# TS-ARM3_0_8.net
KiCad netlist of a schematic drawn in EAGLE
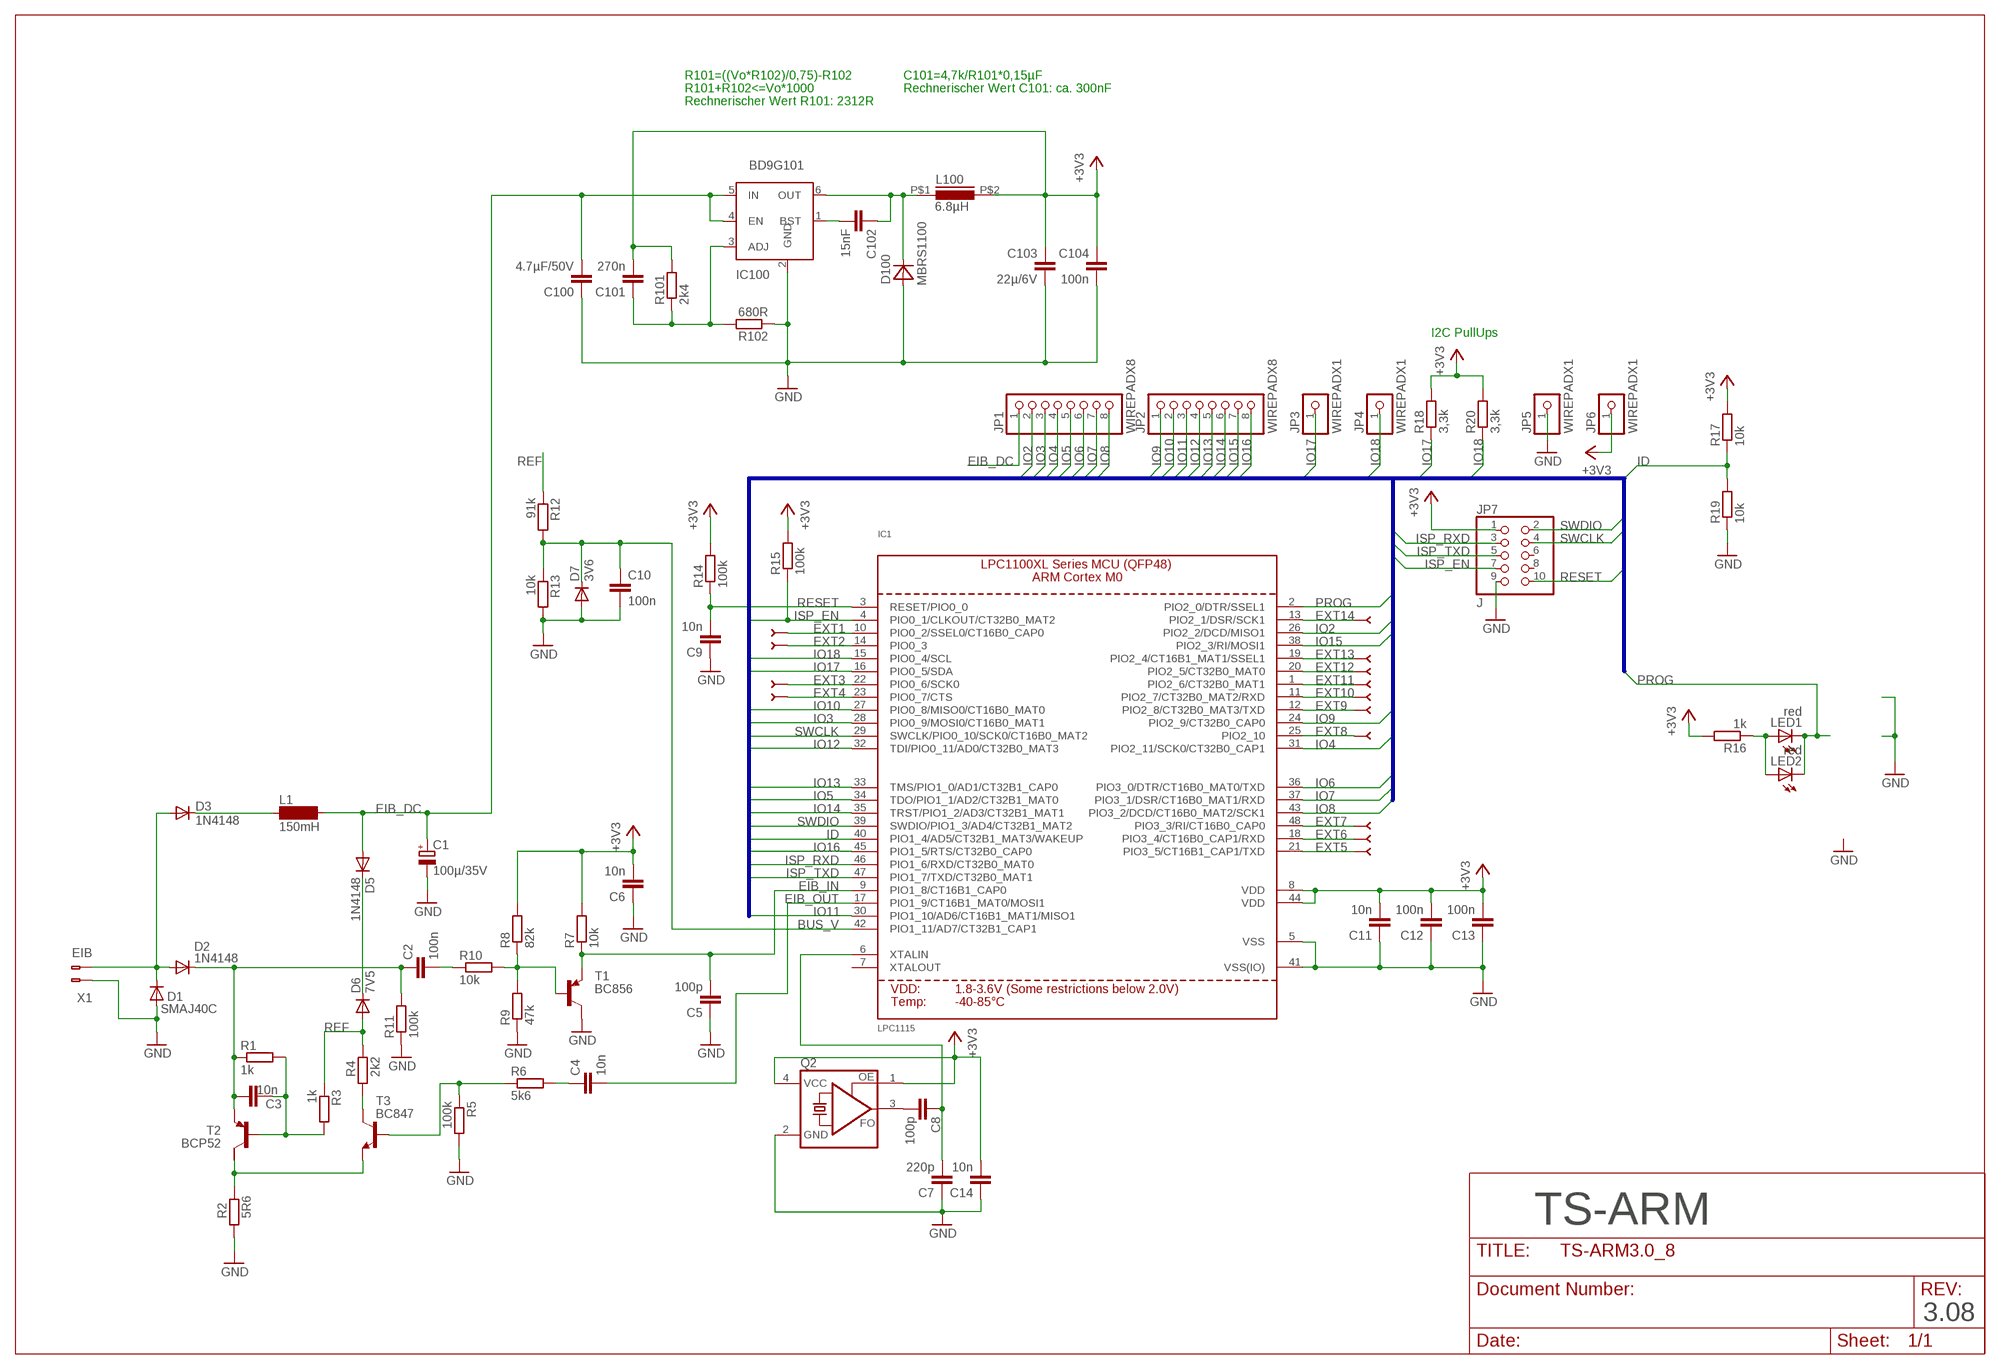
[diagram p0: schematic, sheet 1]

(export (version "E")
  (design (tool "Eeschema 10.0.6"))
  (components
    (comp (ref "C1")
      (value "100µ/35V")
      (footprint "eagle-import:SANYO-OSCON_SMD_C6")
      (libsource (lib "eagle-import") (part "CPOL-EUSANYO_SMD_C6"))
    )
    (comp (ref "C2")
      (value "100n")
      (footprint "eagle-import:C1206")
      (libsource (lib "eagle-import") (part "C-EUC1206"))
    )
    (comp (ref "C3")
      (value "10n")
      (footprint "eagle-import:C1206")
      (libsource (lib "eagle-import") (part "C-EUC1206"))
    )
    (comp (ref "C4")
      (value "10n")
      (footprint "eagle-import:C1206")
      (libsource (lib "eagle-import") (part "C-EUC1206"))
    )
    (comp (ref "C5")
      (value "100p")
      (footprint "eagle-import:C1206")
      (libsource (lib "eagle-import") (part "C-EUC1206"))
    )
    (comp (ref "C6")
      (value "10n")
      (footprint "eagle-import:C1206")
      (libsource (lib "eagle-import") (part "C-EUC1206"))
    )
    (comp (ref "C7")
      (value "220p")
      (footprint "eagle-import:C1206")
      (libsource (lib "eagle-import") (part "C-EUC1206"))
    )
    (comp (ref "C8")
      (value "100p")
      (footprint "eagle-import:C1206")
      (libsource (lib "eagle-import") (part "C-EUC1206"))
    )
    (comp (ref "C9")
      (value "10n")
      (footprint "eagle-import:C1206")
      (libsource (lib "eagle-import") (part "C-EUC1206"))
    )
    (comp (ref "C10")
      (value "100n")
      (footprint "eagle-import:C1206")
      (libsource (lib "eagle-import") (part "C-EUC1206"))
    )
    (comp (ref "C11")
      (value "10n")
      (footprint "eagle-import:C1206")
      (libsource (lib "eagle-import") (part "C-EUC1206"))
    )
    (comp (ref "C12")
      (value "100n")
      (footprint "eagle-import:C1206")
      (libsource (lib "eagle-import") (part "C-EUC1206"))
    )
    (comp (ref "C13")
      (value "100n")
      (footprint "eagle-import:C1206")
      (libsource (lib "eagle-import") (part "C-EUC1206"))
    )
    (comp (ref "C14")
      (value "10n")
      (footprint "eagle-import:C1206")
      (libsource (lib "eagle-import") (part "C-EUC1206"))
    )
    (comp (ref "C100")
      (value "4.7µF/50V")
      (footprint "eagle-import:C1206")
      (libsource (lib "eagle-import") (part "C-EUC1206"))
    )
    (comp (ref "C101")
      (value "270n")
      (footprint "eagle-import:C1206")
      (libsource (lib "eagle-import") (part "C-EUC1206"))
    )
    (comp (ref "C102")
      (value "15nF")
      (footprint "eagle-import:C1206")
      (libsource (lib "eagle-import") (part "C-EUC1206"))
    )
    (comp (ref "C103")
      (value "22µ/6V")
      (footprint "eagle-import:C1206")
      (libsource (lib "eagle-import") (part "C-EUC1206"))
    )
    (comp (ref "C104")
      (value "100n")
      (footprint "eagle-import:C1206")
      (libsource (lib "eagle-import") (part "C-EUC1206"))
    )
    (comp (ref "D1")
      (value "SMAJ40C")
      (footprint "eagle-import:SMB")
      (libsource (lib "eagle-import") (part "D-SMB"))
    )
    (comp (ref "D2")
      (value "1N4148")
      (footprint "eagle-import:MINIMELF")
      (libsource (lib "eagle-import") (part "DIODE-MINIMELF"))
    )
    (comp (ref "D3")
      (value "1N4148")
      (footprint "eagle-import:MINIMELF")
      (libsource (lib "eagle-import") (part "DIODE-MINIMELF"))
    )
    (comp (ref "D5")
      (value "1N4148")
      (footprint "eagle-import:MINIMELF")
      (libsource (lib "eagle-import") (part "DIODE-MINIMELF"))
    )
    (comp (ref "D6")
      (value "7V5")
      (footprint "eagle-import:MINIMELF")
      (libsource (lib "eagle-import") (part "DIODE-MINIMELF"))
    )
    (comp (ref "D7")
      (value "3V6")
      (footprint "eagle-import:MINIMELF")
      (libsource (lib "eagle-import") (part "DIODE-MINIMELF"))
    )
    (comp (ref "D100")
      (value "MBRS1100")
      (footprint "eagle-import:SMA")
      (libsource (lib "eagle-import") (part "MBRA340T3"))
    )
    (comp (ref "IC1")
      (value "LPC1115")
      (footprint "eagle-import:LQFP48")
      (libsource (lib "eagle-import") (part "LPC1113/4/5_QFP48_XLSERIES"))
    )
    (comp (ref "IC100")
      (value "BD9G101")
      (footprint "eagle-import:SOT23-6")
      (libsource (lib "eagle-import") (part "BD9G101GBD9G101G-SOT23-6"))
    )
    (comp (ref "JP1")
      (value "WIREPADX8")
      (footprint "eagle-import:SMD1,27X2,54X8")
      (libsource (lib "eagle-import") (part "WIREPADX8"))
    )
    (comp (ref "JP2")
      (value "WIREPADX8")
      (footprint "eagle-import:SMD1,27X2,54X8")
      (libsource (lib "eagle-import") (part "WIREPADX8"))
    )
    (comp (ref "JP3")
      (value "WIREPADX1")
      (footprint "eagle-import:SMD1,27X2,54")
      (libsource (lib "eagle-import") (part "WIREPADX1"))
    )
    (comp (ref "JP4")
      (value "WIREPADX1")
      (footprint "eagle-import:SMD1,27X2,54")
      (libsource (lib "eagle-import") (part "WIREPADX1"))
    )
    (comp (ref "JP5")
      (value "WIREPADX1")
      (footprint "eagle-import:SMD1,27X2,54")
      (libsource (lib "eagle-import") (part "WIREPADX1"))
    )
    (comp (ref "JP6")
      (value "WIREPADX1")
      (footprint "eagle-import:SMD1,27X2,54")
      (libsource (lib "eagle-import") (part "WIREPADX1"))
    )
    (comp (ref "JP7")
      (value "J")
      (footprint "eagle-import:2X05M")
      (libsource (lib "eagle-import") (part "PINHD-2X05_2.00"))
    )
    (comp (ref "L1")
      (value "150mH")
      (footprint "eagle-import:SD12_1000")
      (libsource (lib "eagle-import") (part "SD12-1000"))
    )
    (comp (ref "L100")
      (value "6.8µH")
      (footprint "eagle-import:PIS2812")
      (libsource (lib "eagle-import") (part "IND_FASTRON_1616FPS"))
    )
    (comp (ref "LED1")
      (value "red")
      (footprint "eagle-import:CHIPLED_1206")
      (libsource (lib "eagle-import") (part "LEDCHIPLED_1206"))
    )
    (comp (ref "LED2")
      (value "red")
      (footprint "eagle-import:LED3MM")
      (libsource (lib "eagle-import") (part "LED3MM"))
    )
    (comp (ref "P1")
      (value "PAD")
      (footprint "eagle-import:PAD")
      (libsource (lib "eagle-import") (part "PAD"))
    )
    (comp (ref "P2")
      (value "PAD")
      (footprint "eagle-import:PAD")
      (libsource (lib "eagle-import") (part "PAD"))
    )
    (comp (ref "P3")
      (value "PAD")
      (footprint "eagle-import:PAD")
      (libsource (lib "eagle-import") (part "PAD"))
    )
    (comp (ref "P4")
      (value "PAD")
      (footprint "eagle-import:PAD")
      (libsource (lib "eagle-import") (part "PAD"))
    )
    (comp (ref "P5")
      (value "PAD")
      (footprint "eagle-import:PAD")
      (libsource (lib "eagle-import") (part "PAD"))
    )
    (comp (ref "P6")
      (value "PAD")
      (footprint "eagle-import:PAD")
      (libsource (lib "eagle-import") (part "PAD"))
    )
    (comp (ref "P7")
      (value "PAD")
      (footprint "eagle-import:PAD")
      (libsource (lib "eagle-import") (part "PAD"))
    )
    (comp (ref "P8")
      (value "PAD")
      (footprint "eagle-import:PAD")
      (libsource (lib "eagle-import") (part "PAD"))
    )
    (comp (ref "P9")
      (value "PAD")
      (footprint "eagle-import:PAD")
      (libsource (lib "eagle-import") (part "PAD"))
    )
    (comp (ref "P10")
      (value "PAD")
      (footprint "eagle-import:PAD")
      (libsource (lib "eagle-import") (part "PAD"))
    )
    (comp (ref "P11")
      (value "PAD")
      (footprint "eagle-import:PAD")
      (libsource (lib "eagle-import") (part "PAD"))
    )
    (comp (ref "P12")
      (value "PAD")
      (footprint "eagle-import:PAD")
      (libsource (lib "eagle-import") (part "PAD"))
    )
    (comp (ref "P13")
      (value "PAD")
      (footprint "eagle-import:PAD")
      (libsource (lib "eagle-import") (part "PAD"))
    )
    (comp (ref "P14")
      (value "PAD")
      (footprint "eagle-import:PAD")
      (libsource (lib "eagle-import") (part "PAD"))
    )
    (comp (ref "Q2")
      (value "ASFL")
      (footprint "eagle-import:ASF")
      (libsource (lib "eagle-import") (part "ASFL"))
    )
    (comp (ref "R1")
      (value "1k")
      (footprint "eagle-import:R1206")
      (libsource (lib "eagle-import") (part "R-EU_R1206"))
    )
    (comp (ref "R2")
      (value "5R6")
      (footprint "eagle-import:R1206")
      (libsource (lib "eagle-import") (part "R-EU_R1206"))
    )
    (comp (ref "R3")
      (value "1k")
      (footprint "eagle-import:R1206")
      (libsource (lib "eagle-import") (part "R-EU_R1206"))
    )
    (comp (ref "R4")
      (value "2k2")
      (footprint "eagle-import:R1206")
      (libsource (lib "eagle-import") (part "R-EU_R1206"))
    )
    (comp (ref "R5")
      (value "100k")
      (footprint "eagle-import:R1206")
      (libsource (lib "eagle-import") (part "R-EU_R1206"))
    )
    (comp (ref "R6")
      (value "5k6")
      (footprint "eagle-import:R1206")
      (libsource (lib "eagle-import") (part "R-EU_R1206"))
    )
    (comp (ref "R7")
      (value "10k")
      (footprint "eagle-import:R1206")
      (libsource (lib "eagle-import") (part "R-EU_R1206"))
    )
    (comp (ref "R8")
      (value "82k")
      (footprint "eagle-import:R1206")
      (libsource (lib "eagle-import") (part "R-EU_R1206"))
    )
    (comp (ref "R9")
      (value "47k")
      (footprint "eagle-import:R1206")
      (libsource (lib "eagle-import") (part "R-EU_R1206"))
    )
    (comp (ref "R10")
      (value "10k")
      (footprint "eagle-import:R1206")
      (libsource (lib "eagle-import") (part "R-EU_R1206"))
    )
    (comp (ref "R11")
      (value "100k")
      (footprint "eagle-import:R1206")
      (libsource (lib "eagle-import") (part "R-EU_R1206"))
    )
    (comp (ref "R12")
      (value "91k")
      (footprint "eagle-import:R1206")
      (libsource (lib "eagle-import") (part "R-EU_R1206"))
    )
    (comp (ref "R13")
      (value "10k")
      (footprint "eagle-import:R1206")
      (libsource (lib "eagle-import") (part "R-EU_R1206"))
    )
    (comp (ref "R14")
      (value "100k")
      (footprint "eagle-import:R1206")
      (libsource (lib "eagle-import") (part "R-EU_R1206"))
    )
    (comp (ref "R15")
      (value "100k")
      (footprint "eagle-import:R1206")
      (libsource (lib "eagle-import") (part "R-EU_R1206"))
    )
    (comp (ref "R16")
      (value "1k")
      (footprint "eagle-import:R1206")
      (libsource (lib "eagle-import") (part "R-EU_R1206"))
    )
    (comp (ref "R17")
      (value "10k")
      (footprint "eagle-import:R1206")
      (libsource (lib "eagle-import") (part "R-EU_R1206"))
    )
    (comp (ref "R18")
      (value "3,3k")
      (footprint "eagle-import:R1206")
      (libsource (lib "eagle-import") (part "R-EU_R1206"))
    )
    (comp (ref "R19")
      (value "10k")
      (footprint "eagle-import:R1206")
      (libsource (lib "eagle-import") (part "R-EU_R1206"))
    )
    (comp (ref "R20")
      (value "3,3k")
      (footprint "eagle-import:R1206")
      (libsource (lib "eagle-import") (part "R-EU_R1206"))
    )
    (comp (ref "R101")
      (value "2k4")
      (footprint "eagle-import:R1206")
      (libsource (lib "eagle-import") (part "R-EU_R1206"))
    )
    (comp (ref "R102")
      (value "680R")
      (footprint "eagle-import:R1206")
      (libsource (lib "eagle-import") (part "R-EU_R1206"))
    )
    (comp (ref "T1")
      (value "BC856")
      (footprint "eagle-import:SOT23-BEC")
      (libsource (lib "eagle-import") (part "BC856SMDB"))
    )
    (comp (ref "T2")
      (value "BCP52")
      (footprint "eagle-import:SOT223")
      (libsource (lib "eagle-import") (part "FZT753SMD"))
    )
    (comp (ref "T3")
      (value "BC847")
      (footprint "eagle-import:SOT23")
      (libsource (lib "eagle-import") (part "BC847"))
    )
    (comp (ref "X1")
      (value "EIB")
      (footprint "eagle-import:BUSKLEMME243-724")
      (libsource (lib "eagle-import") (part "EIB"))
    )
  )
  (nets
    (net (code "1") (name "+3V3") (class "Default")
      (node (ref "C101") (pin "2") (pinfunction "2_2") (pintype "passive"))
      (node (ref "C103") (pin "1") (pinfunction "1_1") (pintype "passive"))
      (node (ref "C104") (pin "1") (pinfunction "1_1") (pintype "passive"))
      (node (ref "C11") (pin "2") (pinfunction "2_2") (pintype "passive"))
      (node (ref "C12") (pin "2") (pinfunction "2_2") (pintype "passive"))
      (node (ref "C13") (pin "2") (pinfunction "2_2") (pintype "passive"))
      (node (ref "C14") (pin "2") (pinfunction "2_2") (pintype "passive"))
      (node (ref "C6") (pin "2") (pinfunction "2_2") (pintype "passive"))
      (node (ref "IC1") (pin "44") (pinfunction "VDD_44") (pintype "power_in"))
      (node (ref "IC1") (pin "8") (pinfunction "VDD_8") (pintype "power_in"))
      (node (ref "JP6") (pin "1") (pinfunction "1_1") (pintype "passive"))
      (node (ref "JP7") (pin "1") (pinfunction "1_1") (pintype "passive"))
      (node (ref "L100") (pin "P$2") (pinfunction "2_P$2") (pintype "passive"))
      (node (ref "Q2") (pin "1") (pinfunction "OE_1") (pintype "input"))
      (node (ref "Q2") (pin "4") (pinfunction "VCC_4") (pintype "power_in"))
      (node (ref "R101") (pin "2") (pinfunction "2_2") (pintype "passive"))
      (node (ref "R14") (pin "2") (pinfunction "2_2") (pintype "passive"))
      (node (ref "R15") (pin "2") (pinfunction "2_2") (pintype "passive"))
      (node (ref "R16") (pin "2") (pinfunction "2_2") (pintype "passive"))
      (node (ref "R17") (pin "2") (pinfunction "2_2") (pintype "passive"))
      (node (ref "R18") (pin "2") (pinfunction "2_2") (pintype "passive"))
      (node (ref "R20") (pin "2") (pinfunction "2_2") (pintype "passive"))
      (node (ref "R7") (pin "2") (pinfunction "2_2") (pintype "passive"))
      (node (ref "R8") (pin "2") (pinfunction "2_2") (pintype "passive"))
    )
    (net (code "2") (name "/BUS_V") (class "Default")
      (node (ref "C10") (pin "2") (pinfunction "2_2") (pintype "passive"))
      (node (ref "D7") (pin "C") (pinfunction "C_C") (pintype "passive"))
      (node (ref "IC1") (pin "42") (pinfunction "PIO1_11/AD7/CT32B1_CAP1_42") (pintype "bidirectional"))
      (node (ref "R12") (pin "2") (pinfunction "2_2") (pintype "passive"))
      (node (ref "R13") (pin "1") (pinfunction "1_1") (pintype "passive"))
    )
    (net (code "3") (name "/EIB_DC") (class "Default")
      (node (ref "C1") (pin "+") (pinfunction "+_+") (pintype "passive"))
      (node (ref "C100") (pin "2") (pinfunction "2_2") (pintype "passive"))
      (node (ref "D5") (pin "A") (pinfunction "A_A") (pintype "passive"))
      (node (ref "IC100") (pin "4") (pinfunction "EN_4") (pintype "input"))
      (node (ref "IC100") (pin "5") (pinfunction "IN_5") (pintype "input"))
      (node (ref "JP1") (pin "1") (pinfunction "1_1") (pintype "passive"))
      (node (ref "L1") (pin "2") (pinfunction "2_2") (pintype "passive"))
    )
    (net (code "4") (name "/EIB_IN") (class "Default")
      (node (ref "C5") (pin "2") (pinfunction "2_2") (pintype "passive"))
      (node (ref "IC1") (pin "9") (pinfunction "PIO1_8/CT16B1_CAP0_9") (pintype "bidirectional"))
      (node (ref "R7") (pin "1") (pinfunction "1_1") (pintype "passive"))
      (node (ref "T1") (pin "E") (pinfunction "E_E") (pintype "passive"))
    )
    (net (code "5") (name "/EIB_OUT") (class "Default")
      (node (ref "C4") (pin "2") (pinfunction "2_2") (pintype "passive"))
      (node (ref "IC1") (pin "17") (pinfunction "PIO1_9/CT16B1_MAT0/MOSI1_17") (pintype "bidirectional"))
    )
    (net (code "6") (name "/EXT1") (class "Default")
      (node (ref "IC1") (pin "10") (pinfunction "PIO0_2/SSEL0/CT16B0_CAP0_10") (pintype "bidirectional"))
      (node (ref "P1") (pin "1") (pinfunction "1_1") (pintype "bidirectional"))
    )
    (net (code "7") (name "/EXT2") (class "Default")
      (node (ref "IC1") (pin "14") (pinfunction "PIO0_3_14") (pintype "bidirectional"))
      (node (ref "P2") (pin "1") (pinfunction "1_1") (pintype "bidirectional"))
    )
    (net (code "8") (name "/EXT3") (class "Default")
      (node (ref "IC1") (pin "22") (pinfunction "PIO0_6/SCK0_22") (pintype "bidirectional"))
      (node (ref "P13") (pin "1") (pinfunction "1_1") (pintype "bidirectional"))
    )
    (net (code "9") (name "/EXT4") (class "Default")
      (node (ref "IC1") (pin "23") (pinfunction "PIO0_7/CTS_23") (pintype "bidirectional"))
      (node (ref "P14") (pin "1") (pinfunction "1_1") (pintype "bidirectional"))
    )
    (net (code "10") (name "/EXT5") (class "Default")
      (node (ref "IC1") (pin "21") (pinfunction "PIO3_5/CT16B1_CAP1/TXD_21") (pintype "bidirectional"))
      (node (ref "P12") (pin "1") (pinfunction "1_1") (pintype "bidirectional"))
    )
    (net (code "11") (name "/EXT6") (class "Default")
      (node (ref "IC1") (pin "18") (pinfunction "PIO3_4/CT16B0_CAP1/RXD_18") (pintype "bidirectional"))
      (node (ref "P11") (pin "1") (pinfunction "1_1") (pintype "bidirectional"))
    )
    (net (code "12") (name "/EXT7") (class "Default")
      (node (ref "IC1") (pin "48") (pinfunction "PIO3_3/RI/CT16B0_CAP0_48") (pintype "bidirectional"))
      (node (ref "P10") (pin "1") (pinfunction "1_1") (pintype "bidirectional"))
    )
    (net (code "13") (name "/EXT8") (class "Default")
      (node (ref "IC1") (pin "25") (pinfunction "PIO2_10_25") (pintype "bidirectional"))
      (node (ref "P6") (pin "1") (pinfunction "1_1") (pintype "bidirectional"))
    )
    (net (code "14") (name "/EXT9") (class "Default")
      (node (ref "IC1") (pin "12") (pinfunction "PIO2_8/CT32B0_MAT3/TXD_12") (pintype "bidirectional"))
      (node (ref "P4") (pin "1") (pinfunction "1_1") (pintype "bidirectional"))
    )
    (net (code "15") (name "/EXT10") (class "Default")
      (node (ref "IC1") (pin "11") (pinfunction "PIO2_7/CT32B0_MAT2/RXD_11") (pintype "bidirectional"))
      (node (ref "P5") (pin "1") (pinfunction "1_1") (pintype "bidirectional"))
    )
    (net (code "16") (name "/EXT11") (class "Default")
      (node (ref "IC1") (pin "1") (pinfunction "PIO2_6/CT32B0_MAT1_1") (pintype "bidirectional"))
      (node (ref "P9") (pin "1") (pinfunction "1_1") (pintype "bidirectional"))
    )
    (net (code "17") (name "/EXT12") (class "Default")
      (node (ref "IC1") (pin "20") (pinfunction "PIO2_5/CT32B0_MAT0_20") (pintype "bidirectional"))
      (node (ref "P8") (pin "1") (pinfunction "1_1") (pintype "bidirectional"))
    )
    (net (code "18") (name "/EXT13") (class "Default")
      (node (ref "IC1") (pin "19") (pinfunction "PIO2_4/CT16B1_MAT1/SSEL1_19") (pintype "bidirectional"))
      (node (ref "P7") (pin "1") (pinfunction "1_1") (pintype "bidirectional"))
    )
    (net (code "19") (name "/EXT14") (class "Default")
      (node (ref "IC1") (pin "13") (pinfunction "PIO2_1/DSR/SCK1_13") (pintype "bidirectional"))
      (node (ref "P3") (pin "1") (pinfunction "1_1") (pintype "bidirectional"))
    )
    (net (code "20") (name "/ID") (class "Default")
      (node (ref "IC1") (pin "40") (pinfunction "PIO1_4/AD5/CT32B1_MAT3/WAKEUP_40") (pintype "bidirectional"))
      (node (ref "R17") (pin "1") (pinfunction "1_1") (pintype "passive"))
      (node (ref "R19") (pin "2") (pinfunction "2_2") (pintype "passive"))
    )
    (net (code "21") (name "/IO2") (class "Default")
      (node (ref "IC1") (pin "26") (pinfunction "PIO2_2/DCD/MISO1_26") (pintype "bidirectional"))
      (node (ref "JP1") (pin "2") (pinfunction "2_2") (pintype "passive"))
    )
    (net (code "22") (name "/IO3") (class "Default")
      (node (ref "IC1") (pin "28") (pinfunction "PIO0_9/MOSI0/CT16B0_MAT1_28") (pintype "bidirectional"))
      (node (ref "JP1") (pin "3") (pinfunction "3_3") (pintype "passive"))
    )
    (net (code "23") (name "/IO4") (class "Default")
      (node (ref "IC1") (pin "31") (pinfunction "PIO2_11/SCK0/CT32B0_CAP1_31") (pintype "bidirectional"))
      (node (ref "JP1") (pin "4") (pinfunction "4_4") (pintype "passive"))
    )
    (net (code "24") (name "/IO5") (class "Default")
      (node (ref "IC1") (pin "34") (pinfunction "TDO/PIO1_1/AD2/CT32B1_MAT0_34") (pintype "bidirectional"))
      (node (ref "JP1") (pin "5") (pinfunction "5_5") (pintype "passive"))
    )
    (net (code "25") (name "/IO6") (class "Default")
      (node (ref "IC1") (pin "36") (pinfunction "PIO3_0/DTR/CT16B0_MAT0/TXD_36") (pintype "bidirectional"))
      (node (ref "JP1") (pin "6") (pinfunction "6_6") (pintype "passive"))
    )
    (net (code "26") (name "/IO7") (class "Default")
      (node (ref "IC1") (pin "37") (pinfunction "PIO3_1/DSR/CT16B0_MAT1/RXD_37") (pintype "bidirectional"))
      (node (ref "JP1") (pin "7") (pinfunction "7_7") (pintype "passive"))
    )
    (net (code "27") (name "/IO8") (class "Default")
      (node (ref "IC1") (pin "43") (pinfunction "PIO3_2/DCD/CT16B0_MAT2/SCK1_43") (pintype "bidirectional"))
      (node (ref "JP1") (pin "8") (pinfunction "8_8") (pintype "passive"))
    )
    (net (code "28") (name "/IO9") (class "Default")
      (node (ref "IC1") (pin "24") (pinfunction "PIO2_9/CT32B0_CAP0_24") (pintype "bidirectional"))
      (node (ref "JP2") (pin "1") (pinfunction "1_1") (pintype "passive"))
    )
    (net (code "29") (name "/IO10") (class "Default")
      (node (ref "IC1") (pin "27") (pinfunction "PIO0_8/MISO0/CT16B0_MAT0_27") (pintype "bidirectional"))
      (node (ref "JP2") (pin "2") (pinfunction "2_2") (pintype "passive"))
    )
    (net (code "30") (name "/IO11") (class "Default")
      (node (ref "IC1") (pin "30") (pinfunction "PIO1_10/AD6/CT16B1_MAT1/MISO1_30") (pintype "bidirectional"))
      (node (ref "JP2") (pin "3") (pinfunction "3_3") (pintype "passive"))
    )
    (net (code "31") (name "/IO12") (class "Default")
      (node (ref "IC1") (pin "32") (pinfunction "TDI/PIO0_11/AD0/CT32B0_MAT3_32") (pintype "bidirectional"))
      (node (ref "JP2") (pin "4") (pinfunction "4_4") (pintype "passive"))
    )
    (net (code "32") (name "/IO13") (class "Default")
      (node (ref "IC1") (pin "33") (pinfunction "TMS/PIO1_0/AD1/CT32B1_CAP0_33") (pintype "bidirectional"))
      (node (ref "JP2") (pin "5") (pinfunction "5_5") (pintype "passive"))
    )
    (net (code "33") (name "/IO14") (class "Default")
      (node (ref "IC1") (pin "35") (pinfunction "TRST/PIO1_2/AD3/CT32B1_MAT1_35") (pintype "bidirectional"))
      (node (ref "JP2") (pin "6") (pinfunction "6_6") (pintype "passive"))
    )
    (net (code "34") (name "/IO15") (class "Default")
      (node (ref "IC1") (pin "38") (pinfunction "PIO2_3/RI/MOSI1_38") (pintype "bidirectional"))
      (node (ref "JP2") (pin "7") (pinfunction "7_7") (pintype "passive"))
    )
    (net (code "35") (name "/IO16") (class "Default")
      (node (ref "IC1") (pin "45") (pinfunction "PIO1_5/RTS/CT32B0_CAP0_45") (pintype "bidirectional"))
      (node (ref "JP2") (pin "8") (pinfunction "8_8") (pintype "passive"))
    )
    (net (code "36") (name "/IO17") (class "Default")
      (node (ref "IC1") (pin "16") (pinfunction "PIO0_5/SDA_16") (pintype "bidirectional"))
      (node (ref "JP3") (pin "1") (pinfunction "1_1") (pintype "passive"))
      (node (ref "R18") (pin "1") (pinfunction "1_1") (pintype "passive"))
    )
    (net (code "37") (name "/IO18") (class "Default")
      (node (ref "IC1") (pin "15") (pinfunction "PIO0_4/SCL_15") (pintype "bidirectional"))
      (node (ref "JP4") (pin "1") (pinfunction "1_1") (pintype "passive"))
      (node (ref "R20") (pin "1") (pinfunction "1_1") (pintype "passive"))
    )
    (net (code "38") (name "/ISP_EN") (class "Default")
      (node (ref "IC1") (pin "4") (pinfunction "PIO0_1/CLKOUT/CT32B0_MAT2_4") (pintype "bidirectional"))
      (node (ref "JP7") (pin "7") (pinfunction "7_7") (pintype "passive"))
      (node (ref "R15") (pin "1") (pinfunction "1_1") (pintype "passive"))
    )
    (net (code "39") (name "/ISP_RXD") (class "Default")
      (node (ref "IC1") (pin "46") (pinfunction "PIO1_6/RXD/CT32B0_MAT0_46") (pintype "bidirectional"))
      (node (ref "JP7") (pin "3") (pinfunction "3_3") (pintype "passive"))
    )
    (net (code "40") (name "/ISP_TXD") (class "Default")
      (node (ref "IC1") (pin "47") (pinfunction "PIO1_7/TXD/CT32B0_MAT1_47") (pintype "bidirectional"))
      (node (ref "JP7") (pin "5") (pinfunction "5_5") (pintype "passive"))
    )
    (net (code "41") (name "/PROG") (class "Default")
      (node (ref "IC1") (pin "2") (pinfunction "PIO2_0/DTR/SSEL1_2") (pintype "bidirectional"))
      (node (ref "LED1") (pin "C") (pinfunction "C_C") (pintype "passive"))
      (node (ref "LED2") (pin "K") (pinfunction "C_K") (pintype "passive"))
    )
    (net (code "42") (name "/REF") (class "Default")
      (node (ref "D6") (pin "A") (pinfunction "A_A") (pintype "passive"))
      (node (ref "R12") (pin "1") (pinfunction "1_1") (pintype "passive"))
      (node (ref "R3") (pin "1") (pinfunction "1_1") (pintype "passive"))
      (node (ref "R4") (pin "2") (pinfunction "2_2") (pintype "passive"))
    )
    (net (code "43") (name "/RESET") (class "Default")
      (node (ref "C9") (pin "2") (pinfunction "2_2") (pintype "passive"))
      (node (ref "IC1") (pin "3") (pinfunction "RESET/PIO0_0_3") (pintype "bidirectional"))
      (node (ref "JP7") (pin "10") (pinfunction "10_10") (pintype "passive"))
      (node (ref "R14") (pin "1") (pinfunction "1_1") (pintype "passive"))
    )
    (net (code "44") (name "/SWCLK") (class "Default")
      (node (ref "IC1") (pin "29") (pinfunction "SWCLK/PIO0_10/SCK0/CT16B0_MAT2_29") (pintype "bidirectional"))
      (node (ref "JP7") (pin "4") (pinfunction "4_4") (pintype "passive"))
    )
    (net (code "45") (name "/SWDIO") (class "Default")
      (node (ref "IC1") (pin "39") (pinfunction "SWDIO/PIO1_3/AD4/CT32B1_MAT2_39") (pintype "bidirectional"))
      (node (ref "JP7") (pin "2") (pinfunction "2_2") (pintype "passive"))
    )
    (net (code "46") (name "GND") (class "Default")
      (node (ref "C1") (pin "-") (pinfunction "-_-") (pintype "passive"))
      (node (ref "C10") (pin "1") (pinfunction "1_1") (pintype "passive"))
      (node (ref "C100") (pin "1") (pinfunction "1_1") (pintype "passive"))
      (node (ref "C103") (pin "2") (pinfunction "2_2") (pintype "passive"))
      (node (ref "C104") (pin "2") (pinfunction "2_2") (pintype "passive"))
      (node (ref "C11") (pin "1") (pinfunction "1_1") (pintype "passive"))
      (node (ref "C12") (pin "1") (pinfunction "1_1") (pintype "passive"))
      (node (ref "C13") (pin "1") (pinfunction "1_1") (pintype "passive"))
      (node (ref "C14") (pin "1") (pinfunction "1_1") (pintype "passive"))
      (node (ref "C5") (pin "1") (pinfunction "1_1") (pintype "passive"))
      (node (ref "C6") (pin "1") (pinfunction "1_1") (pintype "passive"))
      (node (ref "C7") (pin "1") (pinfunction "1_1") (pintype "passive"))
      (node (ref "C9") (pin "1") (pinfunction "1_1") (pintype "passive"))
      (node (ref "D1") (pin "2") (pinfunction "A_2") (pintype "passive"))
      (node (ref "D100") (pin "A") (pinfunction "A_A") (pintype "passive"))
      (node (ref "D7") (pin "A") (pinfunction "A_A") (pintype "passive"))
      (node (ref "IC1") (pin "41") (pinfunction "VSS(IO)_41") (pintype "power_in"))
      (node (ref "IC1") (pin "5") (pinfunction "VSS_5") (pintype "power_in"))
      (node (ref "IC100") (pin "2") (pinfunction "GND_2") (pintype "power_in"))
      (node (ref "JP5") (pin "1") (pinfunction "1_1") (pintype "passive"))
      (node (ref "JP7") (pin "9") (pinfunction "9_9") (pintype "passive"))
      (node (ref "Q2") (pin "2") (pinfunction "GND_2") (pintype "power_in"))
      (node (ref "R102") (pin "1") (pinfunction "1_1") (pintype "passive"))
      (node (ref "R11") (pin "1") (pinfunction "1_1") (pintype "passive"))
      (node (ref "R13") (pin "2") (pinfunction "2_2") (pintype "passive"))
      (node (ref "R19") (pin "1") (pinfunction "1_1") (pintype "passive"))
      (node (ref "R2") (pin "1") (pinfunction "1_1") (pintype "passive"))
      (node (ref "R5") (pin "2") (pinfunction "2_2") (pintype "passive"))
      (node (ref "R9") (pin "1") (pinfunction "1_1") (pintype "passive"))
      (node (ref "T1") (pin "C") (pinfunction "C_C") (pintype "passive"))
      (node (ref "X1") (pin "1") (pinfunction "B-1_1") (pintype "passive"))
    )
    (net (code "47") (name "Net-(C2-Pad2)") (class "Default")
      (node (ref "C2") (pin "2") (pinfunction "2_2") (pintype "passive"))
      (node (ref "R10") (pin "1") (pinfunction "1_1") (pintype "passive"))
    )
    (net (code "48") (name "Net-(C4-Pad1)") (class "Default")
      (node (ref "C4") (pin "1") (pinfunction "1_1") (pintype "passive"))
      (node (ref "R6") (pin "2") (pinfunction "2_2") (pintype "passive"))
    )
    (net (code "49") (name "Net-(D1-C)") (class "Default")
      (node (ref "D1") (pin "1") (pinfunction "C_1") (pintype "passive"))
      (node (ref "D2") (pin "A") (pinfunction "A_A") (pintype "passive"))
      (node (ref "D3") (pin "A") (pinfunction "A_A") (pintype "passive"))
      (node (ref "X1") (pin "2") (pinfunction "B-2_2") (pintype "passive"))
    )
    (net (code "50") (name "Net-(D3-PadC)") (class "Default")
      (node (ref "D3") (pin "C") (pinfunction "C_C") (pintype "passive"))
      (node (ref "L1") (pin "1") (pinfunction "1_1") (pintype "passive"))
    )
    (net (code "51") (name "Net-(D5-PadC)") (class "Default")
      (node (ref "D5") (pin "C") (pinfunction "C_C") (pintype "passive"))
      (node (ref "D6") (pin "C") (pinfunction "C_C") (pintype "passive"))
    )
    (net (code "52") (name "Net-(IC1-XTALIN)") (class "Default")
      (node (ref "C7") (pin "2") (pinfunction "2_2") (pintype "passive"))
      (node (ref "C8") (pin "1") (pinfunction "1_1") (pintype "passive"))
      (node (ref "IC1") (pin "6") (pinfunction "XTALIN_6") (pintype "input"))
    )
    (net (code "53") (name "Net-(IC100-ADJ)") (class "Default")
      (node (ref "C101") (pin "1") (pinfunction "1_1") (pintype "passive"))
      (node (ref "IC100") (pin "3") (pinfunction "ADJ_3") (pintype "passive"))
      (node (ref "R101") (pin "1") (pinfunction "1_1") (pintype "passive"))
      (node (ref "R102") (pin "2") (pinfunction "2_2") (pintype "passive"))
    )
    (net (code "54") (name "Net-(IC100-BST)") (class "Default")
      (node (ref "C102") (pin "2") (pinfunction "2_2") (pintype "passive"))
      (node (ref "IC100") (pin "1") (pinfunction "BST_1") (pintype "output"))
    )
    (net (code "55") (name "Net-(IC100-OUT)") (class "Default")
      (node (ref "C102") (pin "1") (pinfunction "1_1") (pintype "passive"))
      (node (ref "D100") (pin "C") (pinfunction "C_C") (pintype "passive"))
      (node (ref "IC100") (pin "6") (pinfunction "OUT_6") (pintype "output"))
      (node (ref "L100") (pin "P$1") (pinfunction "1_P$1") (pintype "passive"))
    )
    (net (code "56") (name "Net-(LED1-PadA)") (class "Default")
      (node (ref "LED1") (pin "A") (pinfunction "A_A") (pintype "passive"))
      (node (ref "LED2") (pin "A") (pinfunction "A_A") (pintype "passive"))
      (node (ref "R16") (pin "1") (pinfunction "1_1") (pintype "passive"))
    )
    (net (code "57") (name "Net-(Q2-FO)") (class "Default")
      (node (ref "C8") (pin "2") (pinfunction "2_2") (pintype "passive"))
      (node (ref "Q2") (pin "3") (pinfunction "FO_3") (pintype "output"))
    )
    (net (code "58") (name "Net-(R10-Pad2)") (class "Default")
      (node (ref "R10") (pin "2") (pinfunction "2_2") (pintype "passive"))
      (node (ref "R8") (pin "1") (pinfunction "1_1") (pintype "passive"))
      (node (ref "R9") (pin "2") (pinfunction "2_2") (pintype "passive"))
      (node (ref "T1") (pin "B") (pinfunction "B_B") (pintype "passive"))
    )
    (net (code "59") (name "Net-(T2-B)") (class "Default")
      (node (ref "C3") (pin "2") (pinfunction "2_2") (pintype "passive"))
      (node (ref "R1") (pin "2") (pinfunction "2_2") (pintype "passive"))
      (node (ref "R3") (pin "2") (pinfunction "2_2") (pintype "passive"))
      (node (ref "T2") (pin "1") (pinfunction "B_1") (pintype "passive"))
    )
    (net (code "60") (name "Net-(T2-C)") (class "Default")
      (node (ref "R2") (pin "2") (pinfunction "2_2") (pintype "passive"))
      (node (ref "T2") (pin "2") (pinfunction "C_2") (pintype "passive"))
      (node (ref "T3") (pin "2") (pinfunction "E_2") (pintype "passive"))
    )
    (net (code "61") (name "Net-(T2-E)") (class "Default")
      (node (ref "C2") (pin "1") (pinfunction "1_1") (pintype "passive"))
      (node (ref "C3") (pin "1") (pinfunction "1_1") (pintype "passive"))
      (node (ref "D2") (pin "C") (pinfunction "C_C") (pintype "passive"))
      (node (ref "R1") (pin "1") (pinfunction "1_1") (pintype "passive"))
      (node (ref "R11") (pin "2") (pinfunction "2_2") (pintype "passive"))
      (node (ref "T2") (pin "3") (pinfunction "E_3") (pintype "passive"))
    )
    (net (code "62") (name "Net-(T3-B)") (class "Default")
      (node (ref "R5") (pin "1") (pinfunction "1_1") (pintype "passive"))
      (node (ref "R6") (pin "1") (pinfunction "1_1") (pintype "passive"))
      (node (ref "T3") (pin "1") (pinfunction "B_1") (pintype "passive"))
    )
    (net (code "63") (name "Net-(T3-C)") (class "Default")
      (node (ref "R4") (pin "1") (pinfunction "1_1") (pintype "passive"))
      (node (ref "T3") (pin "3") (pinfunction "C_3") (pintype "passive"))
    )
    (net (code "64") (name "unconnected-(IC1-XTALOUT-Pad7)") (class "Default")
      (node (ref "IC1") (pin "7") (pinfunction "XTALOUT_7") (pintype "output"))
    )
    (net (code "65") (name "unconnected-(JP7-Pad6)") (class "Default")
      (node (ref "JP7") (pin "6") (pinfunction "6_6") (pintype "passive"))
    )
    (net (code "66") (name "unconnected-(JP7-Pad8)") (class "Default")
      (node (ref "JP7") (pin "8") (pinfunction "8_8") (pintype "passive"))
    )
    (net (code "67") (name "unconnected-(T2-C{slash}-Pad4)") (class "Default")
      (node (ref "T2") (pin "4") (pinfunction "C/_4") (pintype "passive"))
    )
  )
)
